# TesteKK.net
KiCad netlist of a schematic drawn in Altium Designer
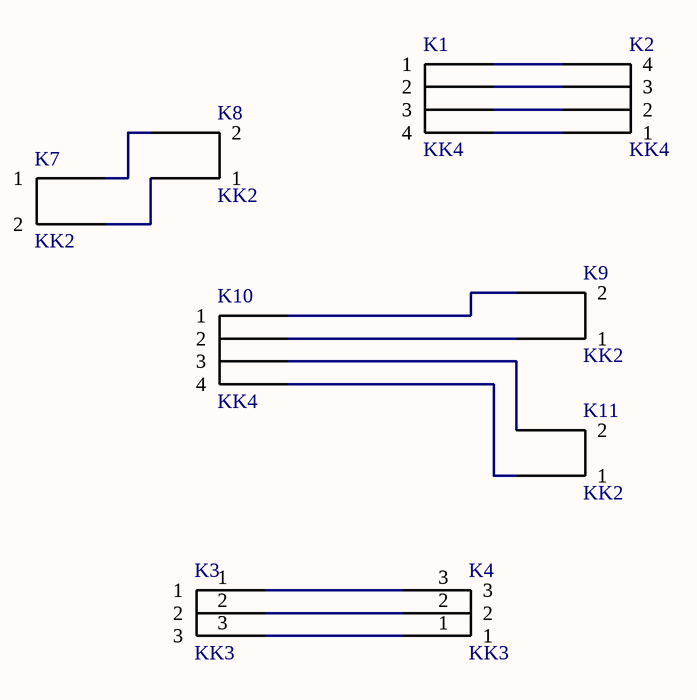
[diagram p0: TesteKK.SchDoc]

(export (version "E")
  (design (tool "Eeschema 10.0.6"))
  (components
    (comp (ref "K1") (value "KK4") (footprint "4-vias") (libsource (lib "Componentes_Open") (part "KK4Vias")))
    (comp (ref "K2") (value "KK4") (footprint "4-vias") (libsource (lib "Componentes_Open") (part "KK4Vias")))
    (comp (ref "K3") (value "KK3") (footprint "3-vias") (libsource (lib "Componentes_Open") (part "KK3Vias")))
    (comp (ref "K4") (value "KK3") (footprint "3-vias") (libsource (lib "Componentes_Open") (part "KK3Vias")))
    (comp (ref "K7") (value "KK2") (footprint "2-vias") (libsource (lib "Componentes_Open") (part "KK2Vias")))
    (comp (ref "K8") (value "KK2") (footprint "2-vias") (libsource (lib "Componentes_Open") (part "KK2Vias")))
    (comp (ref "K9") (value "KK2") (footprint "2-vias") (libsource (lib "Componentes_Open") (part "KK2Vias")))
    (comp (ref "K10")
      (value "KK4")
      (footprint "4-vias")
      (libsource (lib "Componentes_Open") (part "KK4Vias"))
    )
    (comp (ref "K11")
      (value "KK2")
      (footprint "2-vias")
      (libsource (lib "Componentes_Open") (part "KK2Vias"))
    )
  )
  (nets
    (net (code "1") (name "Net-(K1-Pad1)") (class "Default")
      (node (ref "K1") (pin "1") (pinfunction "1_1") (pintype "passive"))
      (node (ref "K2") (pin "4") (pinfunction "4_4") (pintype "passive"))
    )
    (net (code "2") (name "Net-(K1-Pad2)") (class "Default")
      (node (ref "K1") (pin "2") (pinfunction "2_2") (pintype "passive"))
      (node (ref "K2") (pin "3") (pinfunction "3_3") (pintype "passive"))
    )
    (net (code "3") (name "Net-(K1-Pad3)") (class "Default")
      (node (ref "K1") (pin "3") (pinfunction "3_3") (pintype "passive"))
      (node (ref "K2") (pin "2") (pinfunction "2_2") (pintype "passive"))
    )
    (net (code "4") (name "Net-(K1-Pad4)") (class "Default")
      (node (ref "K1") (pin "4") (pinfunction "4_4") (pintype "passive"))
      (node (ref "K2") (pin "1") (pinfunction "1_1") (pintype "passive"))
    )
    (net (code "5") (name "Net-(K3-Pad1)") (class "Default")
      (node (ref "K3") (pin "1") (pinfunction "1_1") (pintype "passive"))
      (node (ref "K4") (pin "3") (pinfunction "3_3") (pintype "passive"))
    )
    (net (code "6") (name "Net-(K3-Pad2)") (class "Default")
      (node (ref "K3") (pin "2") (pinfunction "2_2") (pintype "passive"))
      (node (ref "K4") (pin "2") (pinfunction "2_2") (pintype "passive"))
    )
    (net (code "7") (name "Net-(K3-Pad3)") (class "Default")
      (node (ref "K3") (pin "3") (pinfunction "3_3") (pintype "passive"))
      (node (ref "K4") (pin "1") (pinfunction "1_1") (pintype "passive"))
    )
    (net (code "8") (name "Net-(K7-Pad1)") (class "Default")
      (node (ref "K7") (pin "1") (pinfunction "1_1") (pintype "passive"))
      (node (ref "K8") (pin "2") (pinfunction "2_2") (pintype "passive"))
    )
    (net (code "9") (name "Net-(K7-Pad2)") (class "Default")
      (node (ref "K7") (pin "2") (pinfunction "2_2") (pintype "passive"))
      (node (ref "K8") (pin "1") (pinfunction "1_1") (pintype "passive"))
    )
    (net (code "10") (name "Net-(K10-Pad1)") (class "Default")
      (node (ref "K10") (pin "1") (pinfunction "1_1") (pintype "passive"))
      (node (ref "K9") (pin "2") (pinfunction "2_2") (pintype "passive"))
    )
    (net (code "11") (name "Net-(K10-Pad2)") (class "Default")
      (node (ref "K10") (pin "2") (pinfunction "2_2") (pintype "passive"))
      (node (ref "K9") (pin "1") (pinfunction "1_1") (pintype "passive"))
    )
    (net (code "12") (name "Net-(K10-Pad3)") (class "Default")
      (node (ref "K10") (pin "3") (pinfunction "3_3") (pintype "passive"))
      (node (ref "K11") (pin "2") (pinfunction "2_2") (pintype "passive"))
    )
    (net (code "13") (name "Net-(K10-Pad4)") (class "Default")
      (node (ref "K10") (pin "4") (pinfunction "4_4") (pintype "passive"))
      (node (ref "K11") (pin "1") (pinfunction "1_1") (pintype "passive"))
    )
  )
)
